# RS485.net
KiCad netlist of a schematic drawn in Altium Designer
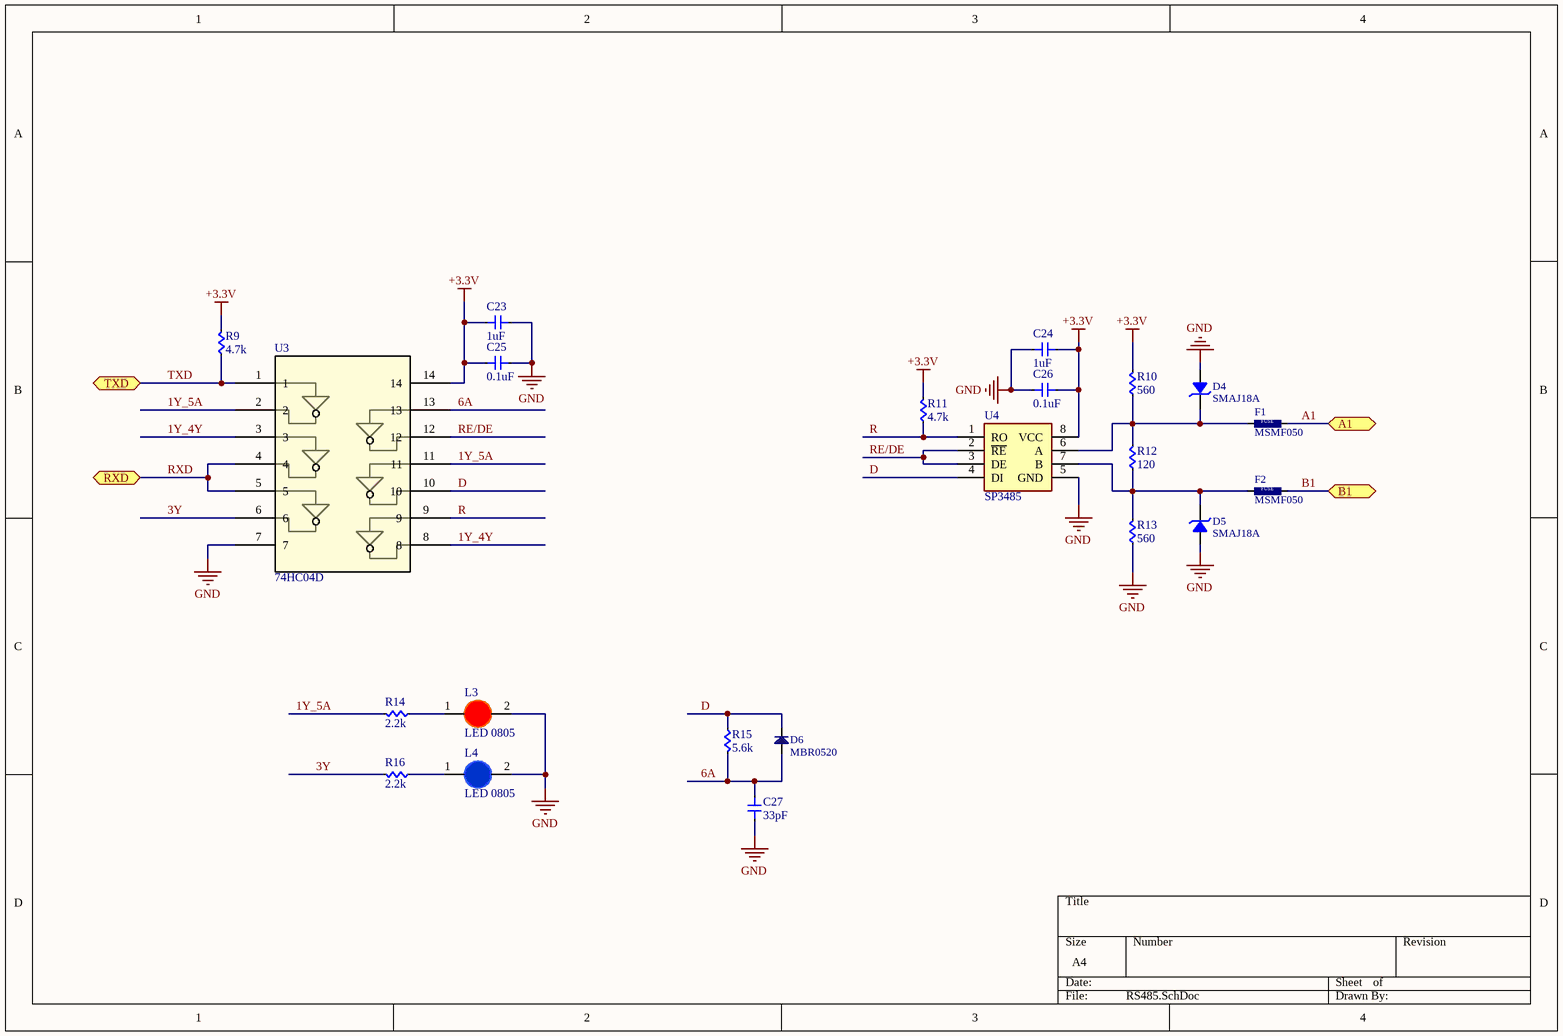
[diagram p0: RS485.SchDoc]

(export (version "E")
  (design (tool "Eeschema 10.0.6"))
  (components
    (comp (ref "C23")
      (value "1uF")
      (footprint "Cap 0603")
      (description "Capacitor SMD 0603")
      (libsource (lib "Altium_Lib_PTK") (part "Cap 0603"))
    )
    (comp (ref "C24")
      (value "1uF")
      (footprint "Cap 0603")
      (description "Capacitor SMD 0603")
      (libsource (lib "Altium_Lib_PTK") (part "Cap 0603"))
    )
    (comp (ref "C25")
      (value "0.1uF")
      (footprint "Cap 0603")
      (description "Capacitor SMD 0603")
      (libsource (lib "Altium_Lib_PTK") (part "Cap 0603"))
    )
    (comp (ref "C26")
      (value "0.1uF")
      (footprint "Cap 0603")
      (description "Capacitor SMD 0603")
      (libsource (lib "Altium_Lib_PTK") (part "Cap 0603"))
    )
    (comp (ref "C27")
      (value "33pF")
      (footprint "Cap 0603")
      (description "Capacitor SMD 0603")
      (libsource (lib "Altium_Lib_PTK") (part "Cap 0603"))
    )
    (comp (ref "D4")
      (value "SMAJ18A")
      (footprint "DO-214AC,SMA")
      (description "Zener Diode")
      (fields (field (name "PUBLISHER") "Altium Limited"))
      (libsource (lib "Altium_Lib_PTK") (part "Diode_TVS"))
    )
    (comp (ref "D5")
      (value "SMAJ18A")
      (footprint "DO-214AC,SMA")
      (description "Zener Diode")
      (fields (field (name "PUBLISHER") "Altium Limited"))
      (libsource (lib "Altium_Lib_PTK") (part "Diode_TVS"))
    )
    (comp (ref "D6")
      (value "MBR0520")
      (footprint "SOD-123")
      (fields (field (name "PUBLISHER") "Altium Limited"))
      (libsource (lib "Altium_Lib_PTK") (part "Didode_MBR0520"))
    )
    (comp (ref "F1")
      (value "MSMF050")
      (footprint "FUSE_PTC")
      (libsource (lib "Altium_Lib_PTK") (part "Fuse_smd"))
    )
    (comp (ref "F2")
      (value "MSMF050")
      (footprint "FUSE_PTC")
      (libsource (lib "Altium_Lib_PTK") (part "Fuse_smd"))
    )
    (comp (ref "L3")
      (value "LED 0805")
      (footprint "LED-0805-Red")
      (description "Dán")
      (libsource (lib "Altium_Lib_PTK") (part "LED 0805 Do"))
    )
    (comp (ref "L4")
      (value "LED 0805")
      (footprint "LED-0805-Blue")
      (description "Dán")
      (libsource (lib "Altium_Lib_PTK") (part "LED 0805 Xanh Duong"))
    )
    (comp (ref "R9")
      (value "4.7k")
      (footprint "RES 0603")
      (description "RES SMD 0603")
      (fields
        (field (name "MANUFACTURER") "Vishay Dale")
        (field (name "MANUFACTURER PART NUMBER") "CRCW040210K0FKED")
      )
      (libsource (lib "Altium_Lib_PTK") (part "RES 0603"))
    )
    (comp (ref "R10")
      (value "560")
      (footprint "RES 0805")
      (description "RES SMD 0805")
      (fields
        (field (name "MANUFACTURER") "Vishay Dale")
        (field (name "MANUFACTURER PART NUMBER") "CRCW040210K0FKED")
      )
      (libsource (lib "Altium_Lib_PTK") (part "RES 0805"))
    )
    (comp (ref "R11")
      (value "4.7k")
      (footprint "RES 0603")
      (description "RES SMD 0603")
      (fields
        (field (name "MANUFACTURER") "Vishay Dale")
        (field (name "MANUFACTURER PART NUMBER") "CRCW040210K0FKED")
      )
      (libsource (lib "Altium_Lib_PTK") (part "RES 0603"))
    )
    (comp (ref "R12")
      (value "120")
      (footprint "RES 0805")
      (description "RES SMD 0805")
      (fields
        (field (name "MANUFACTURER") "Vishay Dale")
        (field (name "MANUFACTURER PART NUMBER") "CRCW040210K0FKED")
      )
      (libsource (lib "Altium_Lib_PTK") (part "RES 0805"))
    )
    (comp (ref "R13")
      (value "560")
      (footprint "RES 0805")
      (description "RES SMD 0805")
      (fields
        (field (name "MANUFACTURER") "Vishay Dale")
        (field (name "MANUFACTURER PART NUMBER") "CRCW040210K0FKED")
      )
      (libsource (lib "Altium_Lib_PTK") (part "RES 0805"))
    )
    (comp (ref "R14")
      (value "2.2k")
      (footprint "RES 0603")
      (description "RES SMD 0603")
      (fields
        (field (name "MANUFACTURER") "Vishay Dale")
        (field (name "MANUFACTURER PART NUMBER") "CRCW040210K0FKED")
      )
      (libsource (lib "Altium_Lib_PTK") (part "RES 0603"))
    )
    (comp (ref "R15")
      (value "5.6k")
      (footprint "RES 0603")
      (description "RES SMD 0603")
      (fields
        (field (name "MANUFACTURER") "Vishay Dale")
        (field (name "MANUFACTURER PART NUMBER") "CRCW040210K0FKED")
      )
      (libsource (lib "Altium_Lib_PTK") (part "RES 0603"))
    )
    (comp (ref "R16")
      (value "2.2k")
      (footprint "RES 0603")
      (description "RES SMD 0603")
      (fields
        (field (name "MANUFACTURER") "Vishay Dale")
        (field (name "MANUFACTURER PART NUMBER") "CRCW040210K0FKED")
      )
      (libsource (lib "Altium_Lib_PTK") (part "RES 0603"))
    )
    (comp (ref "U3")
      (value "74HC04D")
      (footprint "SOIC14_50_285_80X25_SMT")
      (description "Hex Inverter, SOIC14")
      (fields (field (name "COPYRIGHT") "Copyright (C) 2025 Ultra Librarian. All rights reserved."))
      (libsource (lib "Altium_Lib_PTK") (part "74HC04D"))
    )
    (comp (ref "U4")
      (value "SP3485")
      (footprint "SOIC8_50_328_25X90_SMT")
      (libsource (lib "Altium_Lib_PTK") (part "SP3485"))
    )
  )
  (nets
    (net (code "1") (name "+3.3V") (class "Default")
      (node (ref "C23") (pin "1") (pinfunction "1_1") (pintype "passive"))
      (node (ref "C24") (pin "1") (pinfunction "1_1") (pintype "passive"))
      (node (ref "C25") (pin "1") (pinfunction "1_1") (pintype "passive"))
      (node (ref "C26") (pin "1") (pinfunction "1_1") (pintype "passive"))
      (node (ref "R10") (pin "2") (pinfunction "2_2") (pintype "passive"))
      (node (ref "R11") (pin "2") (pinfunction "2_2") (pintype "passive"))
      (node (ref "R9") (pin "2") (pinfunction "2_2") (pintype "passive"))
      (node (ref "U3") (pin "14") (pinfunction "14_14") (pintype "power_in"))
      (node (ref "U4") (pin "8") (pinfunction "VCC_8") (pintype "passive"))
    )
    (net (code "2") (name "/1Y_4Y") (class "Default")
      (node (ref "U3") (pin "3") (pinfunction "3_3") (pintype "passive"))
      (node (ref "U3") (pin "8") (pinfunction "8_8") (pintype "passive"))
    )
    (net (code "3") (name "/1Y_5A") (class "Default")
      (node (ref "R14") (pin "2") (pinfunction "2_2") (pintype "passive"))
      (node (ref "U3") (pin "11") (pinfunction "11_11") (pintype "passive"))
      (node (ref "U3") (pin "2") (pinfunction "2_2") (pintype "passive"))
    )
    (net (code "4") (name "/3Y") (class "Default")
      (node (ref "R16") (pin "2") (pinfunction "2_2") (pintype "passive"))
      (node (ref "U3") (pin "6") (pinfunction "6_6") (pintype "passive"))
    )
    (net (code "5") (name "/6A") (class "Default")
      (node (ref "C27") (pin "2") (pinfunction "2_2") (pintype "passive"))
      (node (ref "D6") (pin "1") (pinfunction "A_1") (pintype "passive"))
      (node (ref "R15") (pin "2") (pinfunction "2_2") (pintype "passive"))
      (node (ref "U3") (pin "13") (pinfunction "13_13") (pintype "passive"))
    )
    (net (code "6") (name "/A1") (class "Default")
      (node (ref "F1") (pin "2") (pinfunction "2_2") (pintype "passive"))
    )
    (net (code "7") (name "/B1") (class "Default")
      (node (ref "F2") (pin "2") (pinfunction "2_2") (pintype "passive"))
    )
    (net (code "8") (name "/D") (class "Default")
      (node (ref "D6") (pin "2") (pinfunction "K_2") (pintype "passive"))
      (node (ref "R15") (pin "1") (pinfunction "1_1") (pintype "passive"))
      (node (ref "U3") (pin "10") (pinfunction "10_10") (pintype "passive"))
      (node (ref "U4") (pin "4") (pinfunction "DI_4") (pintype "passive"))
    )
    (net (code "9") (name "/R") (class "Default")
      (node (ref "R11") (pin "1") (pinfunction "1_1") (pintype "passive"))
      (node (ref "U3") (pin "9") (pinfunction "9_9") (pintype "passive"))
      (node (ref "U4") (pin "1") (pinfunction "RO_1") (pintype "passive"))
    )
    (net (code "10") (name "/RE{slash}DE") (class "Default")
      (node (ref "U3") (pin "12") (pinfunction "12_12") (pintype "passive"))
      (node (ref "U4") (pin "2") (pinfunction "~{RE}_2") (pintype "passive"))
      (node (ref "U4") (pin "3") (pinfunction "DE_3") (pintype "passive"))
    )
    (net (code "11") (name "/RXD") (class "Default")
      (node (ref "U3") (pin "4") (pinfunction "4_4") (pintype "passive"))
      (node (ref "U3") (pin "5") (pinfunction "5_5") (pintype "passive"))
    )
    (net (code "12") (name "/TXD") (class "Default")
      (node (ref "R9") (pin "1") (pinfunction "1_1") (pintype "passive"))
      (node (ref "U3") (pin "1") (pinfunction "1_1") (pintype "passive"))
    )
    (net (code "13") (name "GND") (class "Default")
      (node (ref "C23") (pin "2") (pinfunction "2_2") (pintype "passive"))
      (node (ref "C24") (pin "2") (pinfunction "2_2") (pintype "passive"))
      (node (ref "C25") (pin "2") (pinfunction "2_2") (pintype "passive"))
      (node (ref "C26") (pin "2") (pinfunction "2_2") (pintype "passive"))
      (node (ref "C27") (pin "1") (pinfunction "1_1") (pintype "passive"))
      (node (ref "D4") (pin "1") (pinfunction "A_1") (pintype "passive"))
      (node (ref "D5") (pin "1") (pinfunction "A_1") (pintype "passive"))
      (node (ref "L3") (pin "2") (pinfunction "K_2") (pintype "passive"))
      (node (ref "L4") (pin "2") (pinfunction "K_2") (pintype "passive"))
      (node (ref "R13") (pin "1") (pinfunction "1_1") (pintype "passive"))
      (node (ref "U3") (pin "7") (pinfunction "7_7") (pintype "power_in"))
      (node (ref "U4") (pin "5") (pinfunction "GND_5") (pintype "passive"))
    )
    (net (code "14") (name "Net-(D4-K)") (class "Default")
      (node (ref "D4") (pin "2") (pinfunction "K_2") (pintype "passive"))
      (node (ref "F1") (pin "1") (pinfunction "1_1") (pintype "passive"))
      (node (ref "R10") (pin "1") (pinfunction "1_1") (pintype "passive"))
      (node (ref "R12") (pin "2") (pinfunction "2_2") (pintype "passive"))
      (node (ref "U4") (pin "6") (pinfunction "A_6") (pintype "passive"))
    )
    (net (code "15") (name "Net-(D5-K)") (class "Default")
      (node (ref "D5") (pin "2") (pinfunction "K_2") (pintype "passive"))
      (node (ref "F2") (pin "1") (pinfunction "1_1") (pintype "passive"))
      (node (ref "R12") (pin "1") (pinfunction "1_1") (pintype "passive"))
      (node (ref "R13") (pin "2") (pinfunction "2_2") (pintype "passive"))
      (node (ref "U4") (pin "7") (pinfunction "B_7") (pintype "passive"))
    )
    (net (code "16") (name "Net-(L3-A)") (class "Default")
      (node (ref "L3") (pin "1") (pinfunction "A_1") (pintype "passive"))
      (node (ref "R14") (pin "1") (pinfunction "1_1") (pintype "passive"))
    )
    (net (code "17") (name "Net-(L4-A)") (class "Default")
      (node (ref "L4") (pin "1") (pinfunction "A_1") (pintype "passive"))
      (node (ref "R16") (pin "1") (pinfunction "1_1") (pintype "passive"))
    )
  )
)
